# Ematches.net
KiCad netlist of a schematic drawn in Altium Designer
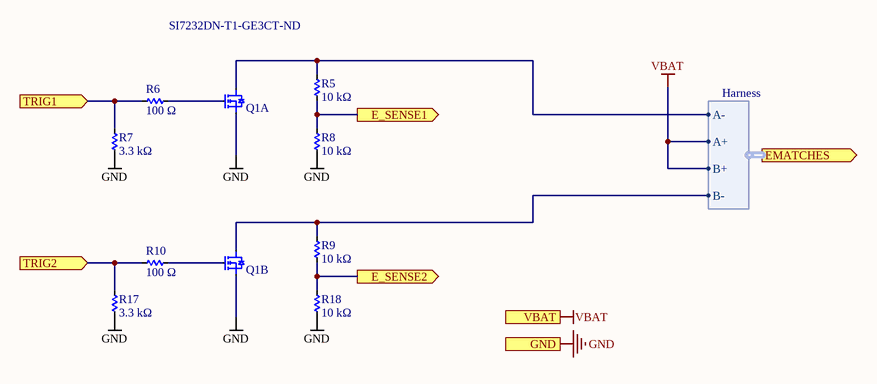
[diagram p0: Ematches.SchDoc]

(export (version "E")
  (design (tool "Eeschema 10.0.6"))
  (components
    (comp (ref "Q1")
      (value "NFET_SI7232DN")
      (footprint "POWERPAK_1212-8_DUAL")
      (description "MOSFET 2N-CH 20V 25A PPAK 1212-8")
      (fields
        (field (name "SUPPLIER PART NUMBER 1") "SI7232DN-T1-GE3CT-ND")
        (field (name "MANUFACTURER") "Vishay Siliconix")
        (field (name "MANUFACTURER PART NUMBER") "SI7232DN-T1-GE3")
      )
      (libsource (lib "SSI") (part "NFET_SI7232DN"))
    )
    (comp (ref "R5")
      (value "__template_resistor")
      (footprint "R0603")
      (description "RES SMD 10K OHM 1% 1/10W 0603")
      (fields
        (field (name "MANUFACTURER PART NUMBER") "RC0603FR-0710KL")
        (field (name "MANUFACTURER") "Yageo")
        (field (name "RESISTANCE") "10 kΩ")
      )
      (libsource (lib "passives") (part "__template_resistor"))
    )
    (comp (ref "R6")
      (value "__template_resistor")
      (footprint "R0603")
      (description "RES SMD 100 OHM 1% 1/10W 0603")
      (fields
        (field (name "MANUFACTURER PART NUMBER") "RC0603FR-07100RL")
        (field (name "MANUFACTURER") "Yageo")
        (field (name "RESISTANCE") "100 Ω")
      )
      (libsource (lib "passives") (part "__template_resistor"))
    )
    (comp (ref "R7")
      (value "__template_resistor")
      (footprint "R0603")
      (description "RES SMD 3.3K OHM 1% 1/10W 0603")
      (fields
        (field (name "MANUFACTURER PART NUMBER") "RC0603FR-073K3L")
        (field (name "MANUFACTURER") "Yageo")
        (field (name "RESISTANCE") "3.3 kΩ")
      )
      (libsource (lib "passives") (part "__template_resistor"))
    )
    (comp (ref "R8")
      (value "__template_resistor")
      (footprint "R0603")
      (description "RES SMD 10K OHM 1% 1/10W 0603")
      (fields
        (field (name "MANUFACTURER PART NUMBER") "RC0603FR-0710KL")
        (field (name "MANUFACTURER") "Yageo")
        (field (name "RESISTANCE") "10 kΩ")
      )
      (libsource (lib "passives") (part "__template_resistor"))
    )
    (comp (ref "R9")
      (value "__template_resistor")
      (footprint "R0603")
      (description "RES SMD 10K OHM 1% 1/10W 0603")
      (fields
        (field (name "MANUFACTURER PART NUMBER") "RC0603FR-0710KL")
        (field (name "MANUFACTURER") "Yageo")
        (field (name "RESISTANCE") "10 kΩ")
      )
      (libsource (lib "passives") (part "__template_resistor"))
    )
    (comp (ref "R10")
      (value "__template_resistor")
      (footprint "R0603")
      (description "RES SMD 100 OHM 1% 1/10W 0603")
      (fields
        (field (name "MANUFACTURER PART NUMBER") "RC0603FR-07100RL")
        (field (name "MANUFACTURER") "Yageo")
        (field (name "RESISTANCE") "100 Ω")
      )
      (libsource (lib "passives") (part "__template_resistor"))
    )
    (comp (ref "R17")
      (value "__template_resistor")
      (footprint "R0603")
      (description "RES SMD 3.3K OHM 1% 1/10W 0603")
      (fields
        (field (name "MANUFACTURER PART NUMBER") "RC0603FR-073K3L")
        (field (name "MANUFACTURER") "Yageo")
        (field (name "RESISTANCE") "3.3 kΩ")
      )
      (libsource (lib "passives") (part "__template_resistor"))
    )
    (comp (ref "R18")
      (value "__template_resistor")
      (footprint "R0603")
      (description "RES SMD 10K OHM 1% 1/10W 0603")
      (fields
        (field (name "MANUFACTURER PART NUMBER") "RC0603FR-0710KL")
        (field (name "MANUFACTURER") "Yageo")
        (field (name "RESISTANCE") "10 kΩ")
      )
      (libsource (lib "passives") (part "__template_resistor"))
    )
  )
  (nets
    (net (code "2") (name "/E_SENSE1") (class "Default")
      (node (ref "R5") (pin "2") (pintype "passive"))
      (node (ref "R8") (pin "1") (pintype "passive"))
    )
    (net (code "3") (name "/E_SENSE2") (class "Default")
      (node (ref "R18") (pin "1") (pintype "passive"))
      (node (ref "R9") (pin "2") (pintype "passive"))
    )
    (net (code "4") (name "/TRIG1") (class "Default")
      (node (ref "R6") (pin "1") (pintype "passive"))
      (node (ref "R7") (pin "2") (pintype "passive"))
    )
    (net (code "5") (name "/TRIG2") (class "Default")
      (node (ref "R10") (pin "1") (pintype "passive"))
      (node (ref "R17") (pin "2") (pintype "passive"))
    )
    (net (code "7") (name "GND") (class "Default")
      (node (ref "Q1") (pin "1") (pintype "passive"))
      (node (ref "Q1") (pin "3") (pintype "passive"))
      (node (ref "R17") (pin "1") (pintype "passive"))
      (node (ref "R18") (pin "2") (pintype "passive"))
      (node (ref "R7") (pin "1") (pintype "passive"))
      (node (ref "R8") (pin "2") (pintype "passive"))
    )
    (net (code "8") (name "Net-(Q1-Pad2)") (class "Default")
      (node (ref "Q1") (pin "2") (pintype "passive"))
      (node (ref "R6") (pin "2") (pintype "passive"))
    )
    (net (code "9") (name "Net-(Q1-Pad4)") (class "Default")
      (node (ref "Q1") (pin "4") (pintype "passive"))
      (node (ref "R10") (pin "2") (pintype "passive"))
    )
    (net (code "10") (name "Net-(Q1-Pad5)") (class "Default")
      (node (ref "Q1") (pin "5") (pintype "passive"))
      (node (ref "R9") (pin "1") (pintype "passive"))
    )
    (net (code "11") (name "Net-(Q1-Pad7)") (class "Default")
      (node (ref "Q1") (pin "7") (pintype "passive"))
      (node (ref "R5") (pin "1") (pintype "passive"))
    )
  )
)
